# SW108_0713.net
KiCad netlist of a schematic drawn in Altium Designer
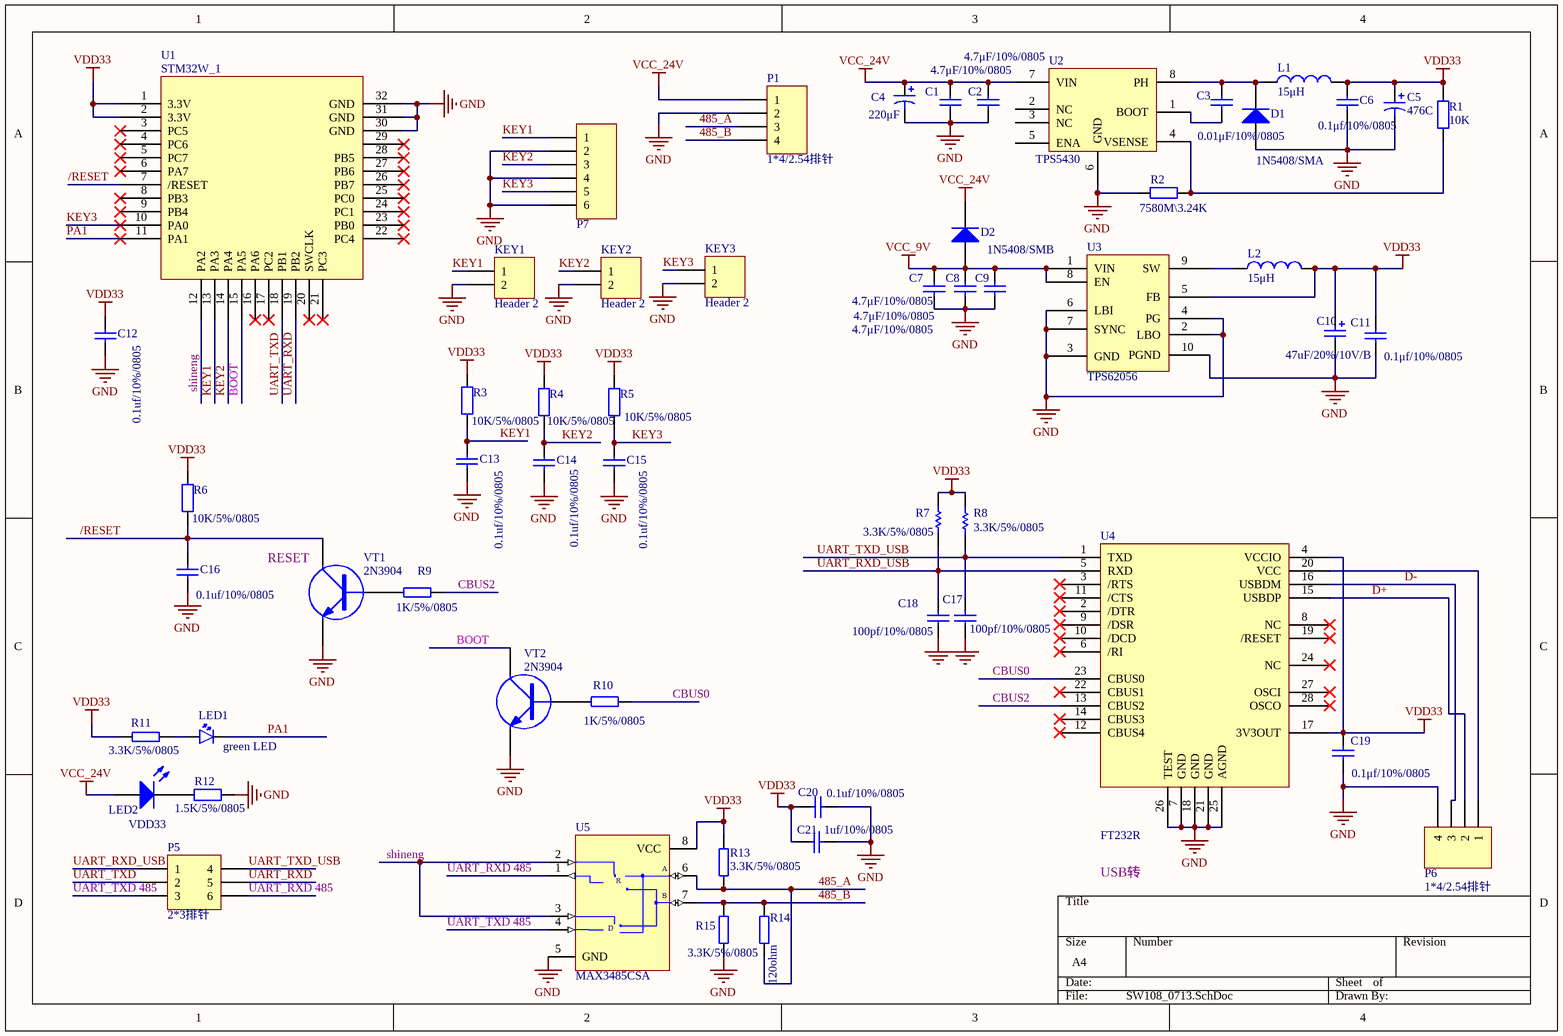
[diagram p0: SW108_0713.SchDoc]

(export (version "E")
  (design (tool "Eeschema 10.0.6"))
  (components
    (comp (ref "C1")
      (value "4.7μF/10%/0805")
      (footprint "C-0805")
      (description "Capacitor")
      (fields (field (name "PUBLISHER") "Altium Limited"))
      (libsource (lib "Miscellaneous Devices") (part "Cap"))
    )
    (comp (ref "C2")
      (value "4.7μF/10%/0805")
      (footprint "C-0805")
      (description "Capacitor")
      (fields (field (name "PUBLISHER") "Altium Limited"))
      (libsource (lib "Miscellaneous Devices") (part "Cap"))
    )
    (comp (ref "C3")
      (value "0.01μF/10%/0805")
      (footprint "C-0805")
      (description "Capacitor")
      (fields (field (name "PUBLISHER") "Altium Limited"))
      (libsource (lib "Miscellaneous Devices") (part "Cap"))
    )
    (comp (ref "C4")
      (value "220μF")
      (footprint "CZ3.0/6.5")
      (description "Polarized Capacitor (Radial)")
      (fields (field (name "PUBLISHER") "Altium Limited"))
      (libsource (lib "Miscellaneous Devices") (part "Cap Pol1"))
    )
    (comp (ref "C5")
      (value "476C")
      (footprint "7343")
      (description "Polarized Capacitor (Radial)")
      (fields (field (name "PUBLISHER") "Altium Limited"))
      (libsource (lib "Miscellaneous Devices") (part "Cap Pol1"))
    )
    (comp (ref "C6")
      (value "0.1μf/10%/0805")
      (footprint "C-0805")
      (description "Capacitor")
      (fields (field (name "PUBLISHER") "Altium Limited"))
      (libsource (lib "Miscellaneous Devices") (part "Cap"))
    )
    (comp (ref "C7")
      (value "4.7μF/10%/0805")
      (footprint "C-0805")
      (description "Capacitor")
      (fields (field (name "PUBLISHER") "Altium Limited"))
      (libsource (lib "Miscellaneous Devices") (part "Cap"))
    )
    (comp (ref "C8")
      (value "4.7μF/10%/0805")
      (footprint "C-0805")
      (description "Capacitor")
      (fields (field (name "PUBLISHER") "Altium Limited"))
      (libsource (lib "Miscellaneous Devices") (part "Cap"))
    )
    (comp (ref "C9")
      (value "4.7μF/10%/0805")
      (footprint "C-0805")
      (description "Capacitor")
      (fields (field (name "PUBLISHER") "Altium Limited"))
      (libsource (lib "Miscellaneous Devices") (part "Cap"))
    )
    (comp (ref "C10")
      (value "47uF/20%/10V/B")
      (footprint "C-TAN-B")
      (libsource (lib "浙江关西电机数据库") (part "CAP_polarity"))
    )
    (comp (ref "C11")
      (value "0.1μf/10%/0805")
      (footprint "C-0805")
      (description "Capacitor")
      (fields (field (name "PUBLISHER") "Altium Limited"))
      (libsource (lib "Miscellaneous Devices") (part "Cap"))
    )
    (comp (ref "C12")
      (value "0.1uf/10%/0805")
      (footprint "C-0805")
      (description "Capacitor")
      (fields (field (name "PUBLISHER") "Altium Limited"))
      (libsource (lib "Miscellaneous Devices") (part "Cap"))
    )
    (comp (ref "C13")
      (value "0.1uf/10%/0805")
      (footprint "C-0805")
      (description "Capacitor")
      (fields (field (name "PUBLISHER") "Altium Limited"))
      (libsource (lib "Miscellaneous Devices") (part "Cap"))
    )
    (comp (ref "C14")
      (value "0.1uf/10%/0805")
      (footprint "C-0805")
      (description "Capacitor")
      (fields (field (name "PUBLISHER") "Altium Limited"))
      (libsource (lib "Miscellaneous Devices") (part "Cap"))
    )
    (comp (ref "C15")
      (value "0.1uf/10%/0805")
      (footprint "C-0805")
      (description "Capacitor")
      (fields (field (name "PUBLISHER") "Altium Limited"))
      (libsource (lib "Miscellaneous Devices") (part "Cap"))
    )
    (comp (ref "C16")
      (value "0.1uf/10%/0805")
      (footprint "C-0805")
      (description "Capacitor")
      (fields (field (name "PUBLISHER") "Altium Limited"))
      (libsource (lib "Miscellaneous Devices") (part "Cap"))
    )
    (comp (ref "C17")
      (value "100pf/10%/0805")
      (footprint "C-0805")
      (description "Capacitor")
      (fields (field (name "PUBLISHER") "Altium Limited"))
      (libsource (lib "Miscellaneous Devices") (part "Cap"))
    )
    (comp (ref "C18")
      (value "100pf/10%/0805")
      (footprint "C-0805")
      (description "Capacitor")
      (fields (field (name "PUBLISHER") "Altium Limited"))
      (libsource (lib "Miscellaneous Devices") (part "Cap"))
    )
    (comp (ref "C19")
      (value "0.1μf/10%/0805")
      (footprint "C-0805")
      (description "Capacitor")
      (fields (field (name "PUBLISHER") "Altium Limited"))
      (libsource (lib "Miscellaneous Devices") (part "Cap"))
    )
    (comp (ref "C20")
      (value "0.1uf/10%/0805")
      (footprint "C-0805")
      (description "Capacitor")
      (fields (field (name "PUBLISHER") "Altium Limited"))
      (libsource (lib "Miscellaneous Devices") (part "Cap"))
    )
    (comp (ref "C21")
      (value "1uf/10%/0805")
      (footprint "C-0805")
      (description "Capacitor")
      (fields (field (name "PUBLISHER") "Altium Limited"))
      (libsource (lib "Miscellaneous Devices") (part "Cap"))
    )
    (comp (ref "D1")
      (value "1N5408/SMA")
      (footprint "SMA 2+")
      (description "3 Amp Medium Power Silicon Rectifier Diode")
      (fields (field (name "PUBLISHER") "Altium Limited"))
      (libsource (lib "Miscellaneous Devices") (part "Diode 1N5408"))
    )
    (comp (ref "D2")
      (value "1N5408/SMB")
      (footprint "smb")
      (description "3 Amp Medium Power Silicon Rectifier Diode")
      (fields (field (name "PUBLISHER") "Altium Limited"))
      (libsource (lib "Miscellaneous Devices") (part "Diode 1N5408"))
    )
    (comp (ref "KEY1")
      (value "Header 2")
      (footprint "TSQG-3")
      (description "Header, 2-Pin")
      (fields (field (name "PUBLISHER") "Altium Limited"))
      (libsource (lib "Miscellaneous Connectors") (part "Header 2"))
    )
    (comp (ref "KEY2")
      (value "Header 2")
      (footprint "TSQG-3")
      (description "Header, 2-Pin")
      (fields (field (name "PUBLISHER") "Altium Limited"))
      (libsource (lib "Miscellaneous Connectors") (part "Header 2"))
    )
    (comp (ref "KEY3")
      (value "Header 2")
      (footprint "TSQG-3")
      (description "Header, 2-Pin")
      (fields (field (name "PUBLISHER") "Altium Limited"))
      (libsource (lib "Miscellaneous Connectors") (part "Header 2"))
    )
    (comp (ref "L1")
      (value "15μH")
      (footprint "GSDS104C2")
      (description "Inductor")
      (fields (field (name "PUBLISHER") "Altium Limited"))
      (libsource (lib "Miscellaneous Devices") (part "Inductor"))
    )
    (comp (ref "L2")
      (value "15μH")
      (footprint "GSDS104C2")
      (description "Inductor")
      (fields (field (name "PUBLISHER") "Altium Limited"))
      (libsource (lib "Miscellaneous Devices") (part "Inductor"))
    )
    (comp (ref "LED1") (value "green LED") (footprint "LED-φ3") (libsource (lib "Haze") (part "LED")))
    (comp (ref "LED2")
      (value "VDD33")
      (footprint "LED-φ3")
      (description "Typical BLUE SiC LED")
      (fields (field (name "PUBLISHER") "Altium Limited"))
      (libsource (lib "Miscellaneous Devices") (part "LED3"))
    )
    (comp (ref "P1")
      (value "1*4/2.54排针")
      (footprint "4kongzhen")
      (description "Header, 4-Pin")
      (fields (field (name "PUBLISHER") "Altium Limited"))
      (libsource (lib "Miscellaneous Connectors") (part "Header 4"))
    )
    (comp (ref "P5")
      (value "2*3排针")
      (footprint "HDR2X3_CEN")
      (description "Header, 3-Pin, Dual row")
      (fields (field (name "PUBLISHER") "Altium Limited"))
      (libsource (lib "Miscellaneous Connectors") (part "Header 3X2A"))
    )
    (comp (ref "P6")
      (value "1*4/2.54排针")
      (footprint "4kongzhen")
      (description "Header, 4-Pin")
      (fields (field (name "PUBLISHER") "Altium Limited"))
      (libsource (lib "") (part "Header 4_1"))
    )
    (comp (ref "P7")
      (value "Header1*6")
      (footprint "PIN-S-2.54-1*6")
      (libsource (lib "SCHLIBRARIES") (part "Header1*6"))
    )
    (comp (ref "R1")
      (value "10K")
      (footprint "R-0805")
      (description "Resistor")
      (fields (field (name "PUBLISHER") "Altium Limited"))
      (libsource (lib "Miscellaneous Devices") (part "Res2"))
    )
    (comp (ref "R2")
      (value "7580~{M}3.24K")
      (footprint "R-0805")
      (description "Resistor")
      (fields (field (name "PUBLISHER") "Altium Limited"))
      (libsource (lib "") (part "Res2_1"))
    )
    (comp (ref "R3")
      (value "10K/5%/0805")
      (footprint "R-0805")
      (description "Resistor")
      (fields (field (name "PUBLISHER") "Altium Limited"))
      (libsource (lib "Miscellaneous Devices") (part "Res2"))
    )
    (comp (ref "R4")
      (value "10K/5%/0805")
      (footprint "R-0805")
      (description "Resistor")
      (fields (field (name "PUBLISHER") "Altium Limited"))
      (libsource (lib "Miscellaneous Devices") (part "Res2"))
    )
    (comp (ref "R5")
      (value "10K/5%/0805")
      (footprint "R-0805")
      (description "Resistor")
      (fields (field (name "PUBLISHER") "Altium Limited"))
      (libsource (lib "Miscellaneous Devices") (part "Res2"))
    )
    (comp (ref "R6")
      (value "10K/5%/0805")
      (footprint "R-0805")
      (description "Resistor")
      (fields (field (name "PUBLISHER") "Altium Limited"))
      (libsource (lib "Miscellaneous Devices") (part "Res2"))
    )
    (comp (ref "R7")
      (value "3.3K/5%/0805")
      (footprint "R-0805")
      (libsource (lib "SCHLIBRARIES") (part "RES_1"))
    )
    (comp (ref "R8")
      (value "3.3K/5%/0805")
      (footprint "R-0805")
      (libsource (lib "SCHLIBRARIES") (part "RES_1"))
    )
    (comp (ref "R9")
      (value "1K/5%/0805")
      (footprint "R-0805")
      (description "R")
      (libsource (lib "Haze") (part "RES"))
    )
    (comp (ref "R10")
      (value "1K/5%/0805")
      (footprint "R-0805")
      (description "R")
      (libsource (lib "Haze") (part "RES"))
    )
    (comp (ref "R11")
      (value "3.3K/5%/0805")
      (footprint "R-0805")
      (description "R")
      (libsource (lib "Haze") (part "RES"))
    )
    (comp (ref "R12")
      (value "1.5K/5%/0805")
      (footprint "R-0805")
      (description "Resistor")
      (fields (field (name "PUBLISHER") "Altium Limited"))
      (libsource (lib "") (part "Res2_1"))
    )
    (comp (ref "R13")
      (value "3.3K/5%/0805")
      (footprint "R-0805")
      (description "R")
      (libsource (lib "Haze") (part "RES"))
    )
    (comp (ref "R14")
      (value "120ohm")
      (footprint "R-0805")
      (description "R")
      (libsource (lib "Haze") (part "RES"))
    )
    (comp (ref "R15")
      (value "3.3K/5%/0805")
      (footprint "R-0805")
      (description "R")
      (libsource (lib "Haze") (part "RES"))
    )
    (comp (ref "U1")
      (value "STM32W_1")
      (footprint "STM32W108-3")
      (libsource (lib "STM32W108-3") (part "STM32W108-3"))
    )
    (comp (ref "U2") (value "TPS5430") (footprint "SO-G8") (libsource (lib "SCHLIBRARIES") (part "TPS5430")))
    (comp (ref "U3")
      (value "TPS62056")
      (footprint "MSOP-10")
      (libsource (lib "SCHLIBRARIES") (part "TPS62056"))
    )
    (comp (ref "U4") (value "FT232R") (footprint "SSOP-28") (libsource (lib "Haze") (part "FT232R")))
    (comp (ref "U5")
      (value "MAX3485CSA")
      (footprint "SO-G8")
      (description "Low-Power, Slew-Rate-Limited RS-485/RS-422 Transceiver")
      (fields (field (name "PUBLISHER") "Altium Limited"))
      (libsource (lib "Maxim Communication Transceiver") (part "MAX485CSA"))
    )
    (comp (ref "VT1")
      (value "2N3904")
      (footprint "SOT23-3")
      (description "NPN Transistor")
      (libsource (lib "Haze") (part "NPN"))
    )
    (comp (ref "VT2")
      (value "2N3904")
      (footprint "SOT23-3")
      (description "NPN Transistor")
      (libsource (lib "Haze") (part "NPN"))
    )
  )
  (nets
    (net (code "1") (name "/485_A") (class "Default")
      (node (ref "P1") (pin "3") (pinfunction "3_3") (pintype "passive"))
      (node (ref "R13") (pin "1") (pinfunction "1_1") (pintype "passive"))
      (node (ref "R14") (pin "2") (pinfunction "2_2") (pintype "passive"))
      (node (ref "U5") (pin "6") (pinfunction "A_6") (pintype "bidirectional"))
    )
    (net (code "2") (name "/485_B") (class "Default")
      (node (ref "P1") (pin "4") (pinfunction "4_4") (pintype "passive"))
      (node (ref "R14") (pin "1") (pinfunction "1_1") (pintype "passive"))
      (node (ref "R15") (pin "2") (pinfunction "2_2") (pintype "passive"))
      (node (ref "U5") (pin "7") (pinfunction "B_7") (pintype "bidirectional"))
    )
    (net (code "3") (name "/BOOT") (class "Default")
      (node (ref "U1") (pin "15") (pinfunction "PA5_15") (pintype "passive"))
      (node (ref "VT2") (pin "3") (pinfunction "C_3") (pintype "passive"))
    )
    (net (code "4") (name "/CBUS0") (class "Default")
      (node (ref "R10") (pin "2") (pinfunction "2_2") (pintype "passive"))
      (node (ref "U4") (pin "23") (pinfunction "CBUS0_23") (pintype "passive"))
    )
    (net (code "5") (name "/CBUS2") (class "Default")
      (node (ref "R9") (pin "2") (pinfunction "2_2") (pintype "passive"))
      (node (ref "U4") (pin "13") (pinfunction "CBUS2_13") (pintype "passive"))
    )
    (net (code "6") (name "/D+") (class "Default")
      (node (ref "P6") (pin "2") (pinfunction "2_2") (pintype "passive"))
      (node (ref "U4") (pin "15") (pinfunction "USBDP_15") (pintype "passive"))
    )
    (net (code "7") (name "/D-") (class "Default")
      (node (ref "P6") (pin "3") (pinfunction "3_3") (pintype "passive"))
      (node (ref "U4") (pin "16") (pinfunction "USBDM_16") (pintype "passive"))
    )
    (net (code "8") (name "/KEY1") (class "Default")
      (node (ref "C13") (pin "2") (pinfunction "2_2") (pintype "passive"))
      (node (ref "KEY1") (pin "1") (pinfunction "1_1") (pintype "passive"))
      (node (ref "P7") (pin "1") (pinfunction "1_1") (pintype "passive"))
      (node (ref "R3") (pin "1") (pinfunction "1_1") (pintype "passive"))
      (node (ref "U1") (pin "13") (pinfunction "PA3_13") (pintype "passive"))
    )
    (net (code "9") (name "/KEY2") (class "Default")
      (node (ref "C14") (pin "2") (pinfunction "2_2") (pintype "passive"))
      (node (ref "KEY2") (pin "1") (pinfunction "1_1") (pintype "passive"))
      (node (ref "P7") (pin "3") (pinfunction "3_3") (pintype "passive"))
      (node (ref "R4") (pin "1") (pinfunction "1_1") (pintype "passive"))
      (node (ref "U1") (pin "14") (pinfunction "PA4_14") (pintype "passive"))
    )
    (net (code "10") (name "/KEY3") (class "Default")
      (node (ref "C15") (pin "2") (pinfunction "2_2") (pintype "passive"))
      (node (ref "KEY3") (pin "1") (pinfunction "1_1") (pintype "passive"))
      (node (ref "P7") (pin "5") (pinfunction "5_5") (pintype "passive"))
      (node (ref "R5") (pin "1") (pinfunction "1_1") (pintype "passive"))
      (node (ref "U1") (pin "10") (pinfunction "PA0_10") (pintype "passive"))
    )
    (net (code "11") (name "/PA1") (class "Default")
      (node (ref "LED1") (pin "2") (pinfunction "K_2") (pintype "passive"))
      (node (ref "U1") (pin "11") (pinfunction "PA1_11") (pintype "passive"))
    )
    (net (code "12") (name "/UART_RXD") (class "Default")
      (node (ref "P5") (pin "5") (pinfunction "5_5") (pintype "passive"))
      (node (ref "U1") (pin "19") (pinfunction "PB2_19") (pintype "passive"))
    )
    (net (code "13") (name "/UART_RXD 485") (class "Default")
      (node (ref "P5") (pin "6") (pinfunction "6_6") (pintype "passive"))
      (node (ref "U5") (pin "1") (pinfunction "RO_1") (pintype "output"))
    )
    (net (code "14") (name "/UART_RXD_USB") (class "Default")
      (node (ref "C18") (pin "2") (pinfunction "2_2") (pintype "passive"))
      (node (ref "P5") (pin "1") (pinfunction "1_1") (pintype "passive"))
      (node (ref "R7") (pin "1") (pinfunction "1_1") (pintype "passive"))
      (node (ref "U4") (pin "5") (pinfunction "RXD_5") (pintype "passive"))
    )
    (net (code "15") (name "/UART_TXD") (class "Default")
      (node (ref "P5") (pin "2") (pinfunction "2_2") (pintype "passive"))
      (node (ref "U1") (pin "18") (pinfunction "PB1_18") (pintype "passive"))
    )
    (net (code "16") (name "/UART_TXD 485") (class "Default")
      (node (ref "P5") (pin "3") (pinfunction "3_3") (pintype "passive"))
      (node (ref "U5") (pin "4") (pinfunction "DI_4") (pintype "input"))
    )
    (net (code "17") (name "/UART_TXD_USB") (class "Default")
      (node (ref "C17") (pin "2") (pinfunction "2_2") (pintype "passive"))
      (node (ref "P5") (pin "4") (pinfunction "4_4") (pintype "passive"))
      (node (ref "R8") (pin "1") (pinfunction "1_1") (pintype "passive"))
      (node (ref "U4") (pin "1") (pinfunction "TXD_1") (pintype "passive"))
    )
    (net (code "18") (name "/shineng") (class "Default")
      (node (ref "U1") (pin "12") (pinfunction "PA2_12") (pintype "passive"))
      (node (ref "U5") (pin "2") (pinfunction "~{RE}_2") (pintype "input"))
      (node (ref "U5") (pin "3") (pinfunction "DE_3") (pintype "input"))
    )
    (net (code "19") (name "/{slash}RESET") (class "Default")
      (node (ref "C16") (pin "2") (pinfunction "2_2") (pintype "passive"))
      (node (ref "R6") (pin "1") (pinfunction "1_1") (pintype "passive"))
      (node (ref "U1") (pin "7") (pinfunction "/RESET_7") (pintype "passive"))
      (node (ref "VT1") (pin "3") (pinfunction "C_3") (pintype "passive"))
    )
    (net (code "20") (name "GND") (class "Default")
      (node (ref "C1") (pin "1") (pinfunction "1_1") (pintype "passive"))
      (node (ref "C10") (pin "2") (pinfunction "2_2") (pintype "passive"))
      (node (ref "C11") (pin "1") (pinfunction "1_1") (pintype "passive"))
      (node (ref "C12") (pin "1") (pinfunction "1_1") (pintype "passive"))
      (node (ref "C13") (pin "1") (pinfunction "1_1") (pintype "passive"))
      (node (ref "C14") (pin "1") (pinfunction "1_1") (pintype "passive"))
      (node (ref "C15") (pin "1") (pinfunction "1_1") (pintype "passive"))
      (node (ref "C16") (pin "1") (pinfunction "1_1") (pintype "passive"))
      (node (ref "C17") (pin "1") (pinfunction "1_1") (pintype "passive"))
      (node (ref "C18") (pin "1") (pinfunction "1_1") (pintype "passive"))
      (node (ref "C19") (pin "1") (pinfunction "1_1") (pintype "passive"))
      (node (ref "C2") (pin "1") (pinfunction "1_1") (pintype "passive"))
      (node (ref "C20") (pin "1") (pinfunction "1_1") (pintype "passive"))
      (node (ref "C21") (pin "1") (pinfunction "1_1") (pintype "passive"))
      (node (ref "C4") (pin "2") (pinfunction "2_2") (pintype "passive"))
      (node (ref "C5") (pin "2") (pinfunction "2_2") (pintype "passive"))
      (node (ref "C6") (pin "1") (pinfunction "1_1") (pintype "passive"))
      (node (ref "C7") (pin "1") (pinfunction "1_1") (pintype "passive"))
      (node (ref "C8") (pin "1") (pinfunction "1_1") (pintype "passive"))
      (node (ref "C9") (pin "1") (pinfunction "1_1") (pintype "passive"))
      (node (ref "D1") (pin "1") (pinfunction "A_1") (pintype "passive"))
      (node (ref "KEY1") (pin "2") (pinfunction "2_2") (pintype "passive"))
      (node (ref "KEY2") (pin "2") (pinfunction "2_2") (pintype "passive"))
      (node (ref "KEY3") (pin "2") (pinfunction "2_2") (pintype "passive"))
      (node (ref "P1") (pin "2") (pinfunction "2_2") (pintype "passive"))
      (node (ref "P6") (pin "4") (pinfunction "4_4") (pintype "passive"))
      (node (ref "P7") (pin "2") (pinfunction "2_2") (pintype "passive"))
      (node (ref "P7") (pin "4") (pinfunction "4_4") (pintype "passive"))
      (node (ref "P7") (pin "6") (pinfunction "6_6") (pintype "passive"))
      (node (ref "R12") (pin "1") (pinfunction "1_1") (pintype "passive"))
      (node (ref "R15") (pin "1") (pinfunction "1_1") (pintype "passive"))
      (node (ref "R2") (pin "2") (pinfunction "2_2") (pintype "passive"))
      (node (ref "U1") (pin "30") (pinfunction "GND_30") (pintype "passive"))
      (node (ref "U1") (pin "31") (pinfunction "GND_31") (pintype "passive"))
      (node (ref "U1") (pin "32") (pinfunction "GND_32") (pintype "passive"))
      (node (ref "U2") (pin "6") (pinfunction "GND_6") (pintype "passive"))
      (node (ref "U3") (pin "10") (pinfunction "PGND_10") (pintype "passive"))
      (node (ref "U3") (pin "2") (pinfunction "LBO_2") (pintype "passive"))
      (node (ref "U3") (pin "3") (pinfunction "GND_3") (pintype "passive"))
      (node (ref "U3") (pin "4") (pinfunction "PG_4") (pintype "passive"))
      (node (ref "U3") (pin "6") (pinfunction "LBI_6") (pintype "passive"))
      (node (ref "U3") (pin "7") (pinfunction "SYNC_7") (pintype "passive"))
      (node (ref "U4") (pin "18") (pinfunction "GND_18") (pintype "passive"))
      (node (ref "U4") (pin "21") (pinfunction "GND_21") (pintype "passive"))
      (node (ref "U4") (pin "25") (pinfunction "AGND_25") (pintype "passive"))
      (node (ref "U4") (pin "26") (pinfunction "TEST_26") (pintype "passive"))
      (node (ref "U4") (pin "7") (pinfunction "GND_7") (pintype "passive"))
      (node (ref "U5") (pin "5") (pinfunction "GND_5") (pintype "power_in"))
      (node (ref "VT1") (pin "2") (pinfunction "E_2") (pintype "passive"))
      (node (ref "VT2") (pin "2") (pinfunction "E_2") (pintype "passive"))
    )
    (net (code "21") (name "Net-(D1-K)") (class "Default")
      (node (ref "C3") (pin "2") (pinfunction "2_2") (pintype "passive"))
      (node (ref "D1") (pin "2") (pinfunction "K_2") (pintype "passive"))
      (node (ref "L1") (pin "1") (pinfunction "1_1") (pintype "passive"))
      (node (ref "U2") (pin "8") (pinfunction "PH_8") (pintype "passive"))
    )
    (net (code "22") (name "Net-(LED1-A)") (class "Default")
      (node (ref "LED1") (pin "1") (pinfunction "A_1") (pintype "passive"))
      (node (ref "R11") (pin "2") (pinfunction "2_2") (pintype "passive"))
    )
    (net (code "23") (name "Net-(LED2-K)") (class "Default")
      (node (ref "LED2") (pin "2") (pinfunction "K_2") (pintype "passive"))
      (node (ref "R12") (pin "2") (pinfunction "2_2") (pintype "passive"))
    )
    (net (code "24") (name "Net-(U2-BOOT)") (class "Default")
      (node (ref "C3") (pin "1") (pinfunction "1_1") (pintype "passive"))
      (node (ref "U2") (pin "1") (pinfunction "BOOT_1") (pintype "passive"))
    )
    (net (code "25") (name "Net-(U2-VSENSE)") (class "Default")
      (node (ref "R1") (pin "1") (pinfunction "1_1") (pintype "passive"))
      (node (ref "R2") (pin "1") (pinfunction "1_1") (pintype "passive"))
      (node (ref "U2") (pin "4") (pinfunction "VSENSE_4") (pintype "passive"))
    )
    (net (code "26") (name "Net-(U3-SW)") (class "Default")
      (node (ref "L2") (pin "1") (pinfunction "1_1") (pintype "passive"))
      (node (ref "U3") (pin "9") (pinfunction "SW_9") (pintype "passive"))
    )
    (net (code "27") (name "Net-(U4-VCC)") (class "Default")
      (node (ref "P6") (pin "1") (pinfunction "1_1") (pintype "passive"))
      (node (ref "U4") (pin "20") (pinfunction "VCC_20") (pintype "passive"))
    )
    (net (code "28") (name "Net-(VT1-B)") (class "Default")
      (node (ref "R9") (pin "1") (pinfunction "1_1") (pintype "passive"))
      (node (ref "VT1") (pin "1") (pinfunction "B_1") (pintype "passive"))
    )
    (net (code "29") (name "Net-(VT2-B)") (class "Default")
      (node (ref "R10") (pin "1") (pinfunction "1_1") (pintype "passive"))
      (node (ref "VT2") (pin "1") (pinfunction "B_1") (pintype "passive"))
    )
    (net (code "30") (name "VCC_9V") (class "Default")
      (node (ref "C7") (pin "2") (pinfunction "2_2") (pintype "passive"))
      (node (ref "C8") (pin "2") (pinfunction "2_2") (pintype "passive"))
      (node (ref "C9") (pin "2") (pinfunction "2_2") (pintype "passive"))
      (node (ref "D2") (pin "1") (pinfunction "A_1") (pintype "passive"))
      (node (ref "U3") (pin "1") (pinfunction "VIN_1") (pintype "passive"))
      (node (ref "U3") (pin "8") (pinfunction "EN_8") (pintype "passive"))
    )
    (net (code "31") (name "VCC_24V") (class "Default")
      (node (ref "C1") (pin "2") (pinfunction "2_2") (pintype "passive"))
      (node (ref "C2") (pin "2") (pinfunction "2_2") (pintype "passive"))
      (node (ref "C4") (pin "1") (pinfunction "1_1") (pintype "passive"))
      (node (ref "D2") (pin "2") (pinfunction "K_2") (pintype "passive"))
      (node (ref "LED2") (pin "1") (pinfunction "A_1") (pintype "passive"))
      (node (ref "P1") (pin "1") (pinfunction "1_1") (pintype "passive"))
      (node (ref "U2") (pin "7") (pinfunction "VIN_7") (pintype "passive"))
    )
    (net (code "32") (name "VDD33") (class "Default")
      (node (ref "C10") (pin "1") (pinfunction "1_1") (pintype "passive"))
      (node (ref "C11") (pin "2") (pinfunction "2_2") (pintype "passive"))
      (node (ref "C12") (pin "2") (pinfunction "2_2") (pintype "passive"))
      (node (ref "C19") (pin "2") (pinfunction "2_2") (pintype "passive"))
      (node (ref "C20") (pin "2") (pinfunction "2_2") (pintype "passive"))
      (node (ref "C21") (pin "2") (pinfunction "2_2") (pintype "passive"))
      (node (ref "C5") (pin "1") (pinfunction "1_1") (pintype "passive"))
      (node (ref "C6") (pin "2") (pinfunction "2_2") (pintype "passive"))
      (node (ref "L1") (pin "2") (pinfunction "2_2") (pintype "passive"))
      (node (ref "L2") (pin "2") (pinfunction "2_2") (pintype "passive"))
      (node (ref "R1") (pin "2") (pinfunction "2_2") (pintype "passive"))
      (node (ref "R11") (pin "1") (pinfunction "1_1") (pintype "passive"))
      (node (ref "R13") (pin "2") (pinfunction "2_2") (pintype "passive"))
      (node (ref "R3") (pin "2") (pinfunction "2_2") (pintype "passive"))
      (node (ref "R4") (pin "2") (pinfunction "2_2") (pintype "passive"))
      (node (ref "R5") (pin "2") (pinfunction "2_2") (pintype "passive"))
      (node (ref "R6") (pin "2") (pinfunction "2_2") (pintype "passive"))
      (node (ref "R7") (pin "2") (pinfunction "2_2") (pintype "passive"))
      (node (ref "R8") (pin "2") (pinfunction "2_2") (pintype "passive"))
      (node (ref "U1") (pin "1") (pinfunction "3.3V_1") (pintype "passive"))
      (node (ref "U1") (pin "2") (pinfunction "3.3V_2") (pintype "passive"))
      (node (ref "U3") (pin "5") (pinfunction "FB_5") (pintype "passive"))
      (node (ref "U4") (pin "17") (pinfunction "3V3OUT_17") (pintype "passive"))
      (node (ref "U4") (pin "4") (pinfunction "VCCIO_4") (pintype "passive"))
      (node (ref "U5") (pin "8") (pinfunction "VCC_8") (pintype "power_in"))
    )
    (net (code "33") (name "unconnected-(U1-PA6-Pad16)") (class "Default")
      (node (ref "U1") (pin "16") (pinfunction "PA6_16") (pintype "passive+no_connect"))
    )
    (net (code "34") (name "unconnected-(U1-PA7-Pad6)") (class "Default")
      (node (ref "U1") (pin "6") (pinfunction "PA7_6") (pintype "passive+no_connect"))
    )
    (net (code "35") (name "unconnected-(U1-PB0-Pad23)") (class "Default")
      (node (ref "U1") (pin "23") (pinfunction "PB0_23") (pintype "passive+no_connect"))
    )
    (net (code "36") (name "unconnected-(U1-PB3-Pad8)") (class "Default")
      (node (ref "U1") (pin "8") (pinfunction "PB3_8") (pintype "passive+no_connect"))
    )
    (net (code "37") (name "unconnected-(U1-PB4-Pad9)") (class "Default")
      (node (ref "U1") (pin "9") (pinfunction "PB4_9") (pintype "passive+no_connect"))
    )
    (net (code "38") (name "unconnected-(U1-PB5-Pad28)") (class "Default")
      (node (ref "U1") (pin "28") (pinfunction "PB5_28") (pintype "passive+no_connect"))
    )
    (net (code "39") (name "unconnected-(U1-PB6-Pad27)") (class "Default")
      (node (ref "U1") (pin "27") (pinfunction "PB6_27") (pintype "passive+no_connect"))
    )
    (net (code "40") (name "unconnected-(U1-PB7-Pad26)") (class "Default")
      (node (ref "U1") (pin "26") (pinfunction "PB7_26") (pintype "passive+no_connect"))
    )
    (net (code "41") (name "unconnected-(U1-PC0-Pad25)") (class "Default")
      (node (ref "U1") (pin "25") (pinfunction "PC0_25") (pintype "passive+no_connect"))
    )
    (net (code "42") (name "unconnected-(U1-PC1-Pad24)") (class "Default")
      (node (ref "U1") (pin "24") (pinfunction "PC1_24") (pintype "passive+no_connect"))
    )
    (net (code "43") (name "unconnected-(U1-PC2-Pad17)") (class "Default")
      (node (ref "U1") (pin "17") (pinfunction "PC2_17") (pintype "passive+no_connect"))
    )
    (net (code "44") (name "unconnected-(U1-PC3-Pad21)") (class "Default")
      (node (ref "U1") (pin "21") (pinfunction "PC3_21") (pintype "passive+no_connect"))
    )
    (net (code "45") (name "unconnected-(U1-PC4-Pad22)") (class "Default")
      (node (ref "U1") (pin "22") (pinfunction "PC4_22") (pintype "passive+no_connect"))
    )
    (net (code "46") (name "unconnected-(U1-PC5-Pad3)") (class "Default")
      (node (ref "U1") (pin "3") (pinfunction "PC5_3") (pintype "passive+no_connect"))
    )
    (net (code "47") (name "unconnected-(U1-PC6-Pad4)") (class "Default")
      (node (ref "U1") (pin "4") (pinfunction "PC6_4") (pintype "passive+no_connect"))
    )
    (net (code "48") (name "unconnected-(U1-PC7-Pad5)") (class "Default")
      (node (ref "U1") (pin "5") (pinfunction "PC7_5") (pintype "passive+no_connect"))
    )
    (net (code "49") (name "unconnected-(U1-Pad29)") (class "Default")
      (node (ref "U1") (pin "29") (pintype "passive+no_connect"))
    )
    (net (code "50") (name "unconnected-(U1-SWCLK-Pad20)") (class "Default")
      (node (ref "U1") (pin "20") (pinfunction "SWCLK_20") (pintype "passive+no_connect"))
    )
    (net (code "51") (name "unconnected-(U2-ENA-Pad5)") (class "Default")
      (node (ref "U2") (pin "5") (pinfunction "ENA_5") (pintype "passive"))
    )
    (net (code "52") (name "unconnected-(U2-NC-Pad2)") (class "Default")
      (node (ref "U2") (pin "2") (pinfunction "NC_2") (pintype "passive"))
    )
    (net (code "53") (name "unconnected-(U2-NC-Pad3)") (class "Default")
      (node (ref "U2") (pin "3") (pinfunction "NC_3") (pintype "passive"))
    )
    (net (code "54") (name "unconnected-(U4-CBUS1-Pad22)") (class "Default")
      (node (ref "U4") (pin "22") (pinfunction "CBUS1_22") (pintype "passive+no_connect"))
    )
    (net (code "55") (name "unconnected-(U4-CBUS3-Pad14)") (class "Default")
      (node (ref "U4") (pin "14") (pinfunction "CBUS3_14") (pintype "passive+no_connect"))
    )
    (net (code "56") (name "unconnected-(U4-CBUS4-Pad12)") (class "Default")
      (node (ref "U4") (pin "12") (pinfunction "CBUS4_12") (pintype "passive+no_connect"))
    )
    (net (code "57") (name "unconnected-(U4-NC-Pad8)") (class "Default")
      (node (ref "U4") (pin "8") (pinfunction "NC_8") (pintype "passive+no_connect"))
    )
    (net (code "58") (name "unconnected-(U4-NC-Pad24)") (class "Default")
      (node (ref "U4") (pin "24") (pinfunction "NC_24") (pintype "passive+no_connect"))
    )
    (net (code "59") (name "unconnected-(U4-OSCI-Pad27)") (class "Default")
      (node (ref "U4") (pin "27") (pinfunction "OSCI_27") (pintype "passive+no_connect"))
    )
    (net (code "60") (name "unconnected-(U4-OSCO-Pad28)") (class "Default")
      (node (ref "U4") (pin "28") (pinfunction "OSCO_28") (pintype "passive+no_connect"))
    )
    (net (code "61") (name "unconnected-(U4-{slash}CTS-Pad11)") (class "Default")
      (node (ref "U4") (pin "11") (pinfunction "/CTS_11") (pintype "passive+no_connect"))
    )
    (net (code "62") (name "unconnected-(U4-{slash}DCD-Pad10)") (class "Default")
      (node (ref "U4") (pin "10") (pinfunction "/DCD_10") (pintype "passive+no_connect"))
    )
    (net (code "63") (name "unconnected-(U4-{slash}DSR-Pad9)") (class "Default")
      (node (ref "U4") (pin "9") (pinfunction "/DSR_9") (pintype "passive+no_connect"))
    )
    (net (code "64") (name "unconnected-(U4-{slash}DTR-Pad2)") (class "Default")
      (node (ref "U4") (pin "2") (pinfunction "/DTR_2") (pintype "passive+no_connect"))
    )
    (net (code "65") (name "unconnected-(U4-{slash}RESET-Pad19)") (class "Default")
      (node (ref "U4") (pin "19") (pinfunction "/RESET_19") (pintype "passive+no_connect"))
    )
    (net (code "66") (name "unconnected-(U4-{slash}RI-Pad6)") (class "Default")
      (node (ref "U4") (pin "6") (pinfunction "/RI_6") (pintype "passive+no_connect"))
    )
    (net (code "67") (name "unconnected-(U4-{slash}RTS-Pad3)") (class "Default")
      (node (ref "U4") (pin "3") (pinfunction "/RTS_3") (pintype "passive+no_connect"))
    )
  )
)
